# Steering_Wheel_Interface_Digital_Inputs.net
KiCad netlist of a schematic drawn in Altium Designer
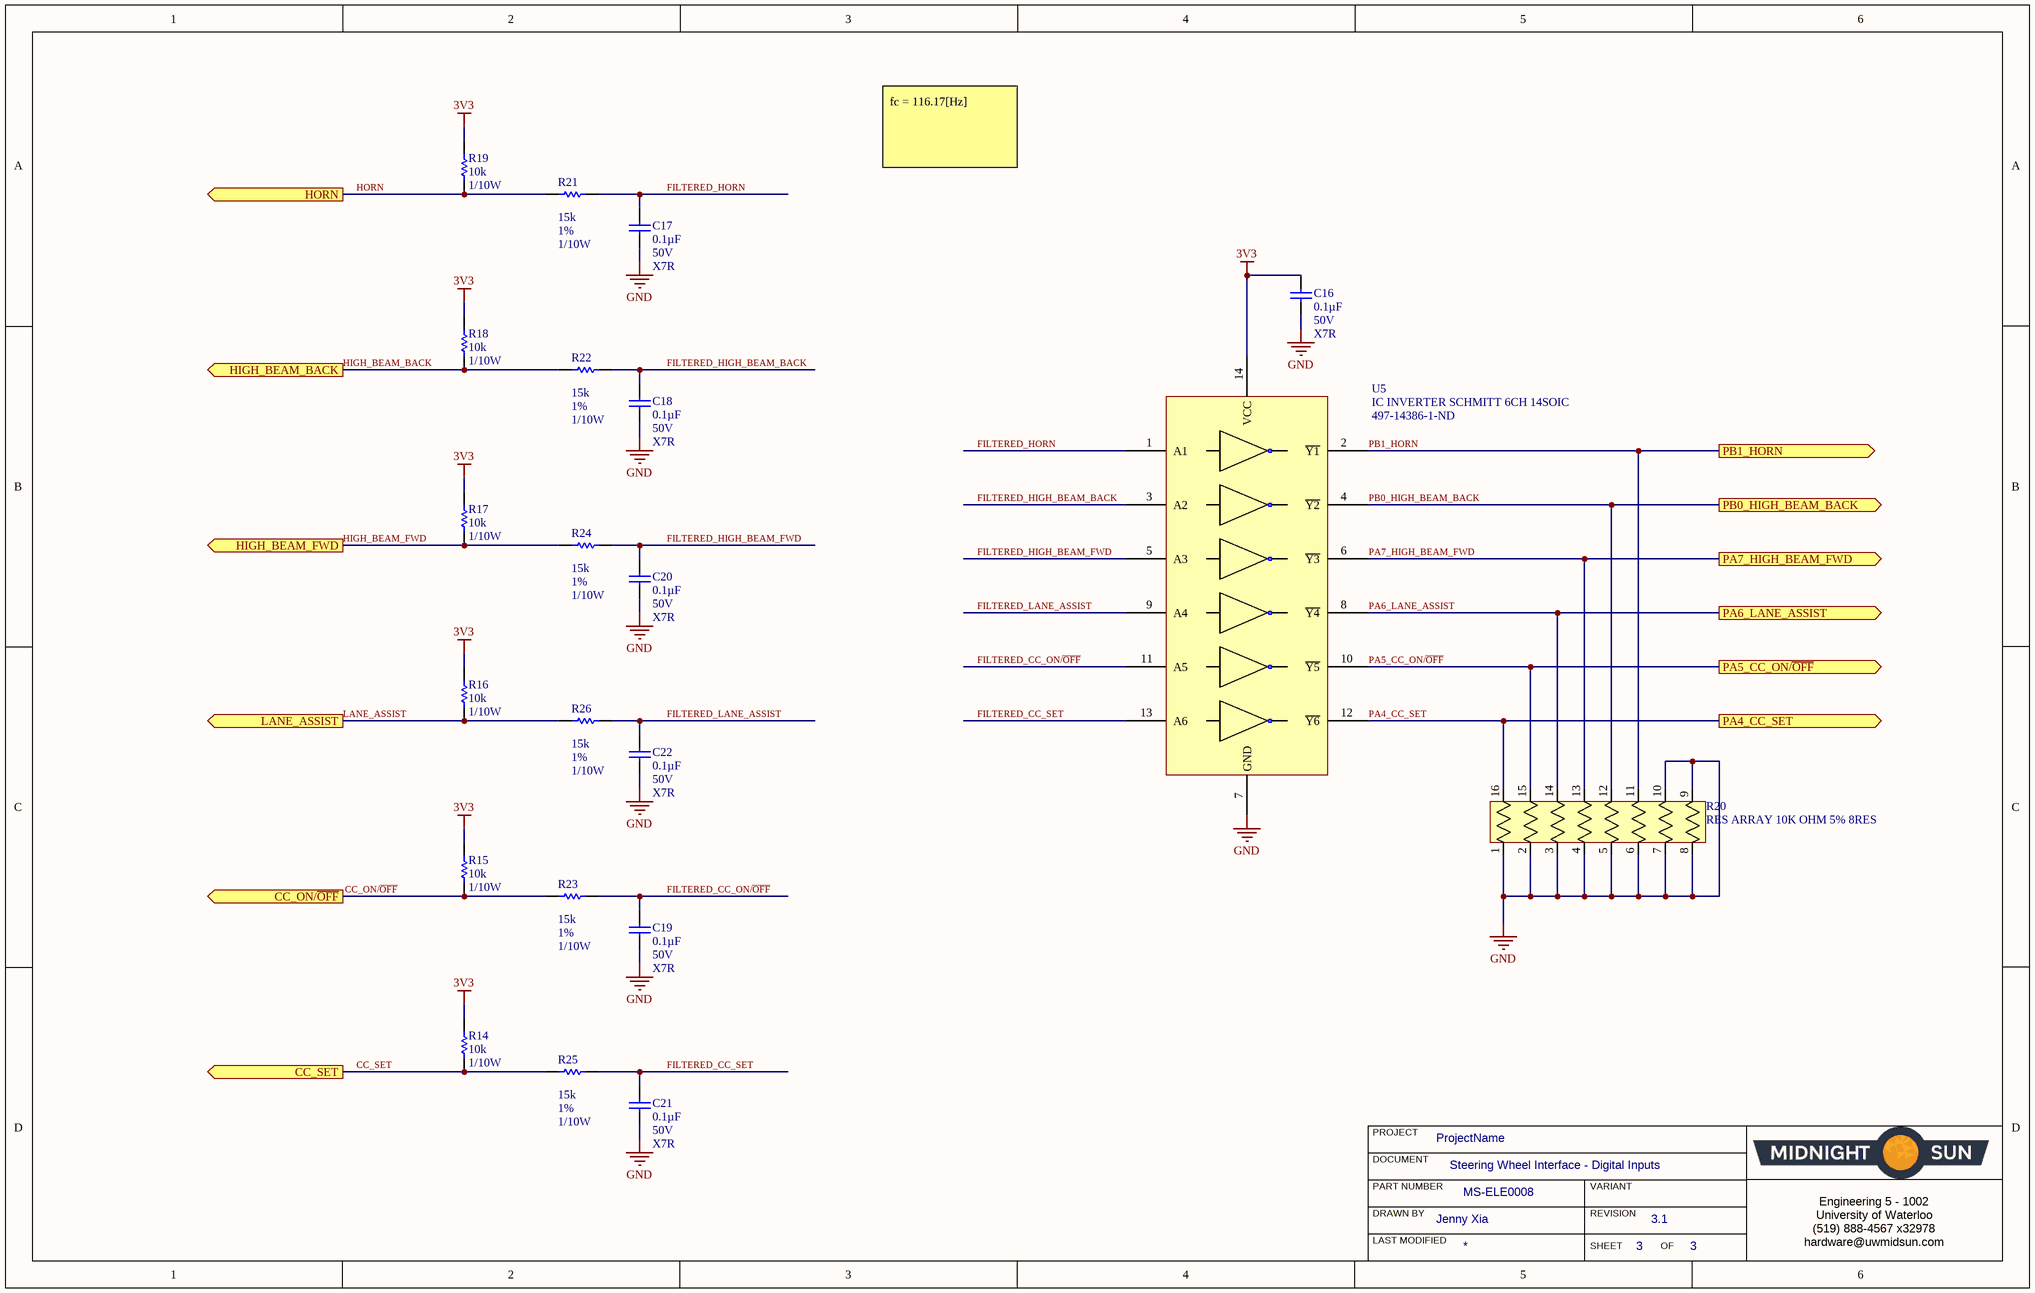
[diagram p0: Steering Wheel Interface Digital Inputs.SchDoc]

(export (version "E")
  (design (tool "Eeschema 10.0.6"))
  (components
    (comp (ref "C16")
      (value "CAP CER 0.1UF 50V 10% X7R 0603")
      (footprint "CAP, 0603")
      (description "0.10µF ±10% 50V Ceramic Capacitor X7R 0603 (1608 Metric)")
      (fields
        (field (name "TOLERANCE") "±10%")
        (field (name "CAPACITANCE") "0.1µF")
        (field (name "VOLTAGE") "50V")
        (field (name "TEMPERATURE COEFFICIENT") "X7R")
      )
      (libsource (lib "Schematic Diagrams") (part "CAP CER 0.1UF 50V 10% X7R 0603"))
    )
    (comp (ref "C17")
      (value "CAP CER 0.1UF 50V 10% X7R 0603")
      (footprint "CAP, 0603")
      (description "0.10µF ±10% 50V Ceramic Capacitor X7R 0603 (1608 Metric)")
      (fields
        (field (name "TOLERANCE") "±10%")
        (field (name "CAPACITANCE") "0.1µF")
        (field (name "VOLTAGE") "50V")
        (field (name "TEMPERATURE COEFFICIENT") "X7R")
      )
      (libsource (lib "Schematic Diagrams") (part "CAP CER 0.1UF 50V 10% X7R 0603"))
    )
    (comp (ref "C18")
      (value "CAP CER 0.1UF 50V 10% X7R 0603")
      (footprint "CAP, 0603")
      (description "0.10µF ±10% 50V Ceramic Capacitor X7R 0603 (1608 Metric)")
      (fields
        (field (name "TOLERANCE") "±10%")
        (field (name "CAPACITANCE") "0.1µF")
        (field (name "VOLTAGE") "50V")
        (field (name "TEMPERATURE COEFFICIENT") "X7R")
      )
      (libsource (lib "Schematic Diagrams") (part "CAP CER 0.1UF 50V 10% X7R 0603"))
    )
    (comp (ref "C19")
      (value "CAP CER 0.1UF 50V 10% X7R 0603")
      (footprint "CAP, 0603")
      (description "0.10µF ±10% 50V Ceramic Capacitor X7R 0603 (1608 Metric)")
      (fields
        (field (name "TOLERANCE") "±10%")
        (field (name "CAPACITANCE") "0.1µF")
        (field (name "VOLTAGE") "50V")
        (field (name "TEMPERATURE COEFFICIENT") "X7R")
      )
      (libsource (lib "Schematic Diagrams") (part "CAP CER 0.1UF 50V 10% X7R 0603"))
    )
    (comp (ref "C20")
      (value "CAP CER 0.1UF 50V 10% X7R 0603")
      (footprint "CAP, 0603")
      (description "0.10µF ±10% 50V Ceramic Capacitor X7R 0603 (1608 Metric)")
      (fields
        (field (name "TOLERANCE") "±10%")
        (field (name "CAPACITANCE") "0.1µF")
        (field (name "VOLTAGE") "50V")
        (field (name "TEMPERATURE COEFFICIENT") "X7R")
      )
      (libsource (lib "Schematic Diagrams") (part "CAP CER 0.1UF 50V 10% X7R 0603"))
    )
    (comp (ref "C21")
      (value "CAP CER 0.1UF 50V 10% X7R 0603")
      (footprint "CAP, 0603")
      (description "0.10µF ±10% 50V Ceramic Capacitor X7R 0603 (1608 Metric)")
      (fields
        (field (name "TOLERANCE") "±10%")
        (field (name "CAPACITANCE") "0.1µF")
        (field (name "VOLTAGE") "50V")
        (field (name "TEMPERATURE COEFFICIENT") "X7R")
      )
      (libsource (lib "Schematic Diagrams") (part "CAP CER 0.1UF 50V 10% X7R 0603"))
    )
    (comp (ref "C22")
      (value "CAP CER 0.1UF 50V 10% X7R 0603")
      (footprint "CAP, 0603")
      (description "0.10µF ±10% 50V Ceramic Capacitor X7R 0603 (1608 Metric)")
      (fields
        (field (name "TOLERANCE") "±10%")
        (field (name "CAPACITANCE") "0.1µF")
        (field (name "VOLTAGE") "50V")
        (field (name "TEMPERATURE COEFFICIENT") "X7R")
      )
      (libsource (lib "Schematic Diagrams") (part "CAP CER 0.1UF 50V 10% X7R 0603"))
    )
    (comp (ref "R14")
      (value "RES 10K OHM 1% 1/10W 0603")
      (footprint "RES, 0603")
      (description "RES SMD 10K OHM 1% 1/10W 0603")
      (fields
        (field (name "TOLERANCE") "±1%")
        (field (name "RESISTANCE") "10k")
        (field (name "POWER") "1/10W")
      )
      (libsource (lib "Schematic Diagrams") (part "RES 10K OHM 1% 1/10W 0603"))
    )
    (comp (ref "R15")
      (value "RES 10K OHM 1% 1/10W 0603")
      (footprint "RES, 0603")
      (description "RES SMD 10K OHM 1% 1/10W 0603")
      (fields
        (field (name "TOLERANCE") "±1%")
        (field (name "RESISTANCE") "10k")
        (field (name "POWER") "1/10W")
      )
      (libsource (lib "Schematic Diagrams") (part "RES 10K OHM 1% 1/10W 0603"))
    )
    (comp (ref "R16")
      (value "RES 10K OHM 1% 1/10W 0603")
      (footprint "RES, 0603")
      (description "RES SMD 10K OHM 1% 1/10W 0603")
      (fields
        (field (name "TOLERANCE") "±1%")
        (field (name "RESISTANCE") "10k")
        (field (name "POWER") "1/10W")
      )
      (libsource (lib "Schematic Diagrams") (part "RES 10K OHM 1% 1/10W 0603"))
    )
    (comp (ref "R17")
      (value "RES 10K OHM 1% 1/10W 0603")
      (footprint "RES, 0603")
      (description "RES SMD 10K OHM 1% 1/10W 0603")
      (fields
        (field (name "TOLERANCE") "±1%")
        (field (name "RESISTANCE") "10k")
        (field (name "POWER") "1/10W")
      )
      (libsource (lib "Schematic Diagrams") (part "RES 10K OHM 1% 1/10W 0603"))
    )
    (comp (ref "R18")
      (value "RES 10K OHM 1% 1/10W 0603")
      (footprint "RES, 0603")
      (description "RES SMD 10K OHM 1% 1/10W 0603")
      (fields
        (field (name "TOLERANCE") "±1%")
        (field (name "RESISTANCE") "10k")
        (field (name "POWER") "1/10W")
      )
      (libsource (lib "Schematic Diagrams") (part "RES 10K OHM 1% 1/10W 0603"))
    )
    (comp (ref "R19")
      (value "RES 10K OHM 1% 1/10W 0603")
      (footprint "RES, 0603")
      (description "RES SMD 10K OHM 1% 1/10W 0603")
      (fields
        (field (name "TOLERANCE") "±1%")
        (field (name "RESISTANCE") "10k")
        (field (name "POWER") "1/10W")
      )
      (libsource (lib "Schematic Diagrams") (part "RES 10K OHM 1% 1/10W 0603"))
    )
    (comp (ref "R20")
      (value "RES ARRAY 10K OHM 5% 8RES")
      (footprint "RES ARRAY, 8 POS 1506")
      (description "RES ARRAY SMD 10K 5% 62.5mW 1506")
      (fields
        (field (name "MANUFACTURER_PART_NUMBER") "EXB-2HV103JV")
        (field (name "MANUFACTURER") "Panasonic Electronic Components")
        (field (name "COPYRIGHT") "Copyright (C) 2015 Accelerated Designs. All rights reserved")
      )
      (libsource (lib "Schematic Diagrams") (part "RES ARRAY 10K OHM 5% 8RES EXB-2HV103JV"))
    )
    (comp (ref "R21")
      (value "RES SMD 15K OHM 1% 1/10W 0603")
      (footprint "RES, 0603")
      (description "15 kOhms ±1% 0.1W, 1/10W Chip Resistor 0603 (1608 Metric) Moisture Resistant Thick Film")
      (fields
        (field (name "RESISTANCE") "15k")
        (field (name "TOLERANCE") "1%")
        (field (name "MAX POWER DISSIPATION") "1/10W")
        (field (name "MANUFACTURER") "Yageo")
        (field (name "MANUFACTURER PART NUMBER") "RC0603FR-0715KL")
      )
      (libsource (lib "Schematic Diagrams") (part "RES SMD 15K OHM 1% 1/10W 0603"))
    )
    (comp (ref "R22")
      (value "RES SMD 15K OHM 1% 1/10W 0603")
      (footprint "RES, 0603")
      (description "15 kOhms ±1% 0.1W, 1/10W Chip Resistor 0603 (1608 Metric) Moisture Resistant Thick Film")
      (fields
        (field (name "RESISTANCE") "15k")
        (field (name "TOLERANCE") "1%")
        (field (name "MAX POWER DISSIPATION") "1/10W")
        (field (name "MANUFACTURER") "Yageo")
        (field (name "MANUFACTURER PART NUMBER") "RC0603FR-0715KL")
      )
      (libsource (lib "Schematic Diagrams") (part "RES SMD 15K OHM 1% 1/10W 0603"))
    )
    (comp (ref "R23")
      (value "RES SMD 15K OHM 1% 1/10W 0603")
      (footprint "RES, 0603")
      (description "15 kOhms ±1% 0.1W, 1/10W Chip Resistor 0603 (1608 Metric) Moisture Resistant Thick Film")
      (fields
        (field (name "RESISTANCE") "15k")
        (field (name "TOLERANCE") "1%")
        (field (name "MAX POWER DISSIPATION") "1/10W")
        (field (name "MANUFACTURER") "Yageo")
        (field (name "MANUFACTURER PART NUMBER") "RC0603FR-0715KL")
      )
      (libsource (lib "Schematic Diagrams") (part "RES SMD 15K OHM 1% 1/10W 0603"))
    )
    (comp (ref "R24")
      (value "RES SMD 15K OHM 1% 1/10W 0603")
      (footprint "RES, 0603")
      (description "15 kOhms ±1% 0.1W, 1/10W Chip Resistor 0603 (1608 Metric) Moisture Resistant Thick Film")
      (fields
        (field (name "RESISTANCE") "15k")
        (field (name "TOLERANCE") "1%")
        (field (name "MAX POWER DISSIPATION") "1/10W")
        (field (name "MANUFACTURER") "Yageo")
        (field (name "MANUFACTURER PART NUMBER") "RC0603FR-0715KL")
      )
      (libsource (lib "Schematic Diagrams") (part "RES SMD 15K OHM 1% 1/10W 0603"))
    )
    (comp (ref "R25")
      (value "RES SMD 15K OHM 1% 1/10W 0603")
      (footprint "RES, 0603")
      (description "15 kOhms ±1% 0.1W, 1/10W Chip Resistor 0603 (1608 Metric) Moisture Resistant Thick Film")
      (fields
        (field (name "RESISTANCE") "15k")
        (field (name "TOLERANCE") "1%")
        (field (name "MAX POWER DISSIPATION") "1/10W")
        (field (name "MANUFACTURER") "Yageo")
        (field (name "MANUFACTURER PART NUMBER") "RC0603FR-0715KL")
      )
      (libsource (lib "Schematic Diagrams") (part "RES SMD 15K OHM 1% 1/10W 0603"))
    )
    (comp (ref "R26")
      (value "RES SMD 15K OHM 1% 1/10W 0603")
      (footprint "RES, 0603")
      (description "15 kOhms ±1% 0.1W, 1/10W Chip Resistor 0603 (1608 Metric) Moisture Resistant Thick Film")
      (fields
        (field (name "RESISTANCE") "15k")
        (field (name "TOLERANCE") "1%")
        (field (name "MAX POWER DISSIPATION") "1/10W")
        (field (name "MANUFACTURER") "Yageo")
        (field (name "MANUFACTURER PART NUMBER") "RC0603FR-0715KL")
      )
      (libsource (lib "Schematic Diagrams") (part "RES SMD 15K OHM 1% 1/10W 0603"))
    )
    (comp (ref "U5")
      (value "IC INVERTER SCHMITT 6CH 14SOIC")
      (footprint "IC INVERTER SCHMITT 6CH 14TSSOP")
      (description "Inverter IC 6 Channel Schmitt Trigger 14-SOIC")
      (fields
        (field (name "MANUFACTURER") "STMicroelectronics")
        (field (name "MANUFACTURER PART NUMBER") "M74HC14YRM13TR")
        (field (name "SUPPLIER PART NUMBER 1") "497-14386-1-ND")
      )
      (libsource (lib "Schematic Diagrams") (part "IC INVERTER SCHMITT 6CH 14TSSOP"))
    )
  )
  (nets
    (net (code "1") (name "/CC_ON{slash}~{OFF}") (class "Default")
      (node (ref "R15") (pin "2") (pinfunction "2_2") (pintype "passive"))
      (node (ref "R23") (pin "2") (pinfunction "2_2") (pintype "passive"))
    )
    (net (code "2") (name "/CC_SET") (class "Default")
      (node (ref "R14") (pin "2") (pinfunction "2_2") (pintype "passive"))
      (node (ref "R25") (pin "2") (pinfunction "2_2") (pintype "passive"))
    )
    (net (code "3") (name "/FILTERED_CC_ON{slash}~{OFF}") (class "Default")
      (node (ref "C19") (pin "1") (pinfunction "1_1") (pintype "passive"))
      (node (ref "R23") (pin "1") (pinfunction "1_1") (pintype "passive"))
      (node (ref "U5") (pin "11") (pinfunction "A5_11") (pintype "passive"))
    )
    (net (code "4") (name "/FILTERED_CC_SET") (class "Default")
      (node (ref "C21") (pin "1") (pinfunction "1_1") (pintype "passive"))
      (node (ref "R25") (pin "1") (pinfunction "1_1") (pintype "passive"))
      (node (ref "U5") (pin "13") (pinfunction "A6_13") (pintype "passive"))
    )
    (net (code "5") (name "/FILTERED_HIGH_BEAM_BACK") (class "Default")
      (node (ref "C18") (pin "1") (pinfunction "1_1") (pintype "passive"))
      (node (ref "R22") (pin "1") (pinfunction "1_1") (pintype "passive"))
      (node (ref "U5") (pin "3") (pinfunction "A2_3") (pintype "passive"))
    )
    (net (code "6") (name "/FILTERED_HIGH_BEAM_FWD") (class "Default")
      (node (ref "C20") (pin "1") (pinfunction "1_1") (pintype "passive"))
      (node (ref "R24") (pin "1") (pinfunction "1_1") (pintype "passive"))
      (node (ref "U5") (pin "5") (pinfunction "A3_5") (pintype "passive"))
    )
    (net (code "7") (name "/FILTERED_HORN") (class "Default")
      (node (ref "C17") (pin "1") (pinfunction "1_1") (pintype "passive"))
      (node (ref "R21") (pin "1") (pinfunction "1_1") (pintype "passive"))
      (node (ref "U5") (pin "1") (pinfunction "A1_1") (pintype "passive"))
    )
    (net (code "8") (name "/FILTERED_LANE_ASSIST") (class "Default")
      (node (ref "C22") (pin "1") (pinfunction "1_1") (pintype "passive"))
      (node (ref "R26") (pin "1") (pinfunction "1_1") (pintype "passive"))
      (node (ref "U5") (pin "9") (pinfunction "A4_9") (pintype "passive"))
    )
    (net (code "9") (name "/HIGH_BEAM_BACK") (class "Default")
      (node (ref "R18") (pin "2") (pinfunction "2_2") (pintype "passive"))
      (node (ref "R22") (pin "2") (pinfunction "2_2") (pintype "passive"))
    )
    (net (code "10") (name "/HIGH_BEAM_FWD") (class "Default")
      (node (ref "R17") (pin "2") (pinfunction "2_2") (pintype "passive"))
      (node (ref "R24") (pin "2") (pinfunction "2_2") (pintype "passive"))
    )
    (net (code "11") (name "/HORN") (class "Default")
      (node (ref "R19") (pin "2") (pinfunction "2_2") (pintype "passive"))
      (node (ref "R21") (pin "2") (pinfunction "2_2") (pintype "passive"))
    )
    (net (code "12") (name "/LANE_ASSIST") (class "Default")
      (node (ref "R16") (pin "2") (pinfunction "2_2") (pintype "passive"))
      (node (ref "R26") (pin "2") (pinfunction "2_2") (pintype "passive"))
    )
    (net (code "13") (name "/PA4_CC_SET") (class "Default")
      (node (ref "R20") (pin "16") (pinfunction "16_16") (pintype "passive"))
      (node (ref "U5") (pin "12") (pinfunction "~{Y6}_12") (pintype "passive"))
    )
    (net (code "14") (name "/PA5_CC_ON{slash}~{OFF}") (class "Default")
      (node (ref "R20") (pin "15") (pinfunction "15_15") (pintype "passive"))
      (node (ref "U5") (pin "10") (pinfunction "~{Y5}_10") (pintype "passive"))
    )
    (net (code "15") (name "/PA6_LANE_ASSIST") (class "Default")
      (node (ref "R20") (pin "14") (pinfunction "14_14") (pintype "passive"))
      (node (ref "U5") (pin "8") (pinfunction "~{Y4}_8") (pintype "passive"))
    )
    (net (code "16") (name "/PA7_HIGH_BEAM_FWD") (class "Default")
      (node (ref "R20") (pin "13") (pinfunction "13_13") (pintype "passive"))
      (node (ref "U5") (pin "6") (pinfunction "~{Y3}_6") (pintype "passive"))
    )
    (net (code "17") (name "/PB0_HIGH_BEAM_BACK") (class "Default")
      (node (ref "R20") (pin "12") (pinfunction "12_12") (pintype "passive"))
      (node (ref "U5") (pin "4") (pinfunction "~{Y2}_4") (pintype "passive"))
    )
    (net (code "18") (name "/PB1_HORN") (class "Default")
      (node (ref "R20") (pin "11") (pinfunction "11_11") (pintype "passive"))
      (node (ref "U5") (pin "2") (pinfunction "~{Y1}_2") (pintype "passive"))
    )
    (net (code "19") (name "3V3") (class "Default")
      (node (ref "C16") (pin "1") (pinfunction "1_1") (pintype "passive"))
      (node (ref "R14") (pin "1") (pinfunction "1_1") (pintype "passive"))
      (node (ref "R15") (pin "1") (pinfunction "1_1") (pintype "passive"))
      (node (ref "R16") (pin "1") (pinfunction "1_1") (pintype "passive"))
      (node (ref "R17") (pin "1") (pinfunction "1_1") (pintype "passive"))
      (node (ref "R18") (pin "1") (pinfunction "1_1") (pintype "passive"))
      (node (ref "R19") (pin "1") (pinfunction "1_1") (pintype "passive"))
      (node (ref "U5") (pin "14") (pinfunction "VCC_14") (pintype "passive"))
    )
    (net (code "20") (name "GND") (class "Default")
      (node (ref "C16") (pin "2") (pinfunction "2_2") (pintype "passive"))
      (node (ref "C17") (pin "2") (pinfunction "2_2") (pintype "passive"))
      (node (ref "C18") (pin "2") (pinfunction "2_2") (pintype "passive"))
      (node (ref "C19") (pin "2") (pinfunction "2_2") (pintype "passive"))
      (node (ref "C20") (pin "2") (pinfunction "2_2") (pintype "passive"))
      (node (ref "C21") (pin "2") (pinfunction "2_2") (pintype "passive"))
      (node (ref "C22") (pin "2") (pinfunction "2_2") (pintype "passive"))
      (node (ref "R20") (pin "1") (pinfunction "1_1") (pintype "passive"))
      (node (ref "R20") (pin "10") (pinfunction "10_10") (pintype "passive"))
      (node (ref "R20") (pin "2") (pinfunction "2_2") (pintype "passive"))
      (node (ref "R20") (pin "3") (pinfunction "3_3") (pintype "passive"))
      (node (ref "R20") (pin "4") (pinfunction "4_4") (pintype "passive"))
      (node (ref "R20") (pin "5") (pinfunction "5_5") (pintype "passive"))
      (node (ref "R20") (pin "6") (pinfunction "6_6") (pintype "passive"))
      (node (ref "R20") (pin "7") (pinfunction "7_7") (pintype "passive"))
      (node (ref "R20") (pin "8") (pinfunction "8_8") (pintype "passive"))
      (node (ref "R20") (pin "9") (pinfunction "9_9") (pintype "passive"))
      (node (ref "U5") (pin "7") (pinfunction "GND_7") (pintype "passive"))
    )
  )
)
